# Preamp.net
KiCad netlist of a schematic drawn in EAGLE
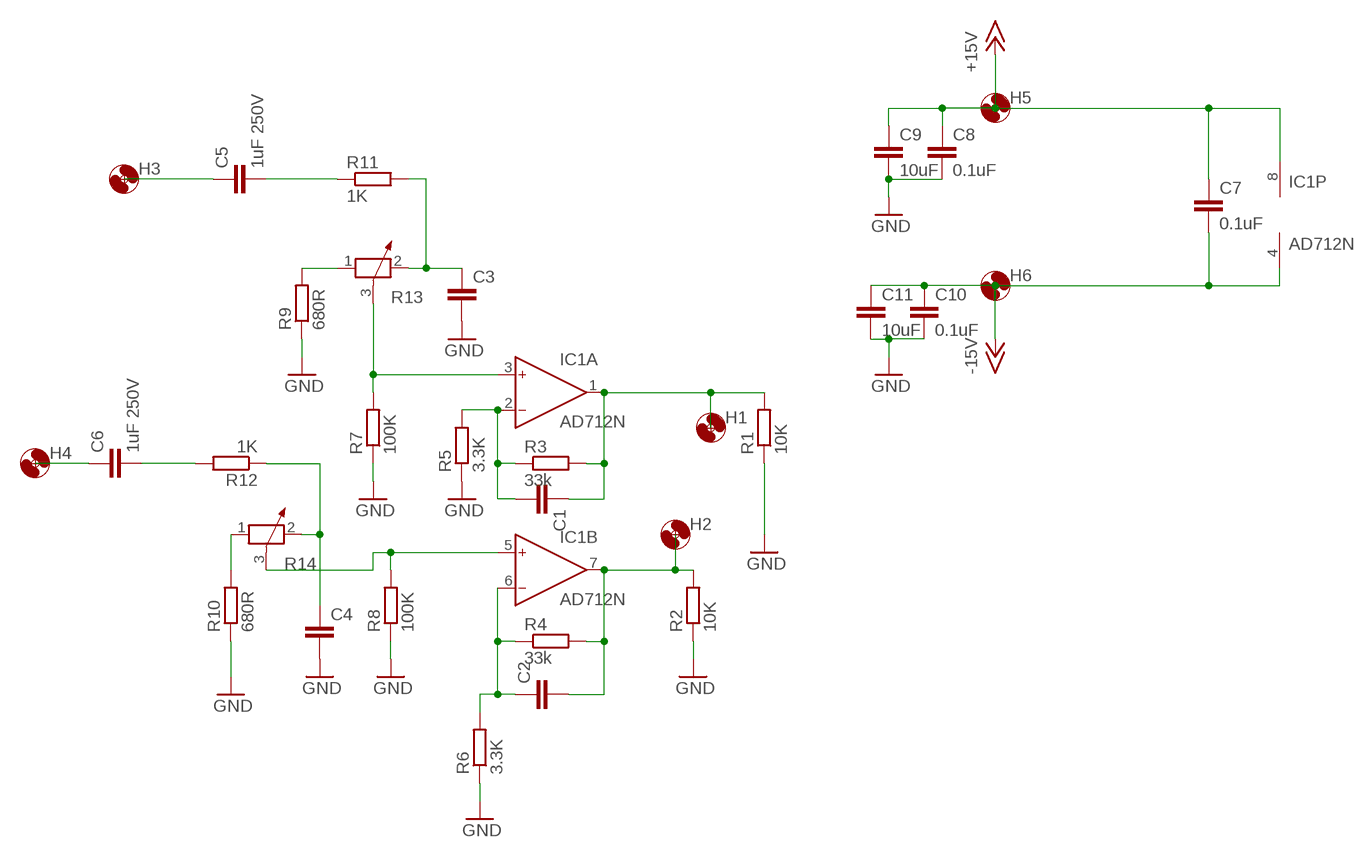
[diagram p0: schematic, sheet 1]

(export (version "E")
  (design (tool "Eeschema 10.0.6"))
  (components
    (comp (ref "C1")
      (value "C-EUC0805K")
      (footprint "eagle-import:C0805K")
      (libsource (lib "eagle-import") (part "C-EUC0805K"))
    )
    (comp (ref "C2")
      (value "C-EUC0805K")
      (footprint "eagle-import:C0805K")
      (libsource (lib "eagle-import") (part "C-EUC0805K"))
    )
    (comp (ref "C3")
      (value "C-EUC0805K")
      (footprint "eagle-import:C0805K")
      (libsource (lib "eagle-import") (part "C-EUC0805K"))
    )
    (comp (ref "C4")
      (value "C-EUC0805K")
      (footprint "eagle-import:C0805K")
      (libsource (lib "eagle-import") (part "C-EUC0805K"))
    )
    (comp (ref "C5")
      (value "1uF 250V")
      (footprint "eagle-import:C0805K")
      (libsource (lib "eagle-import") (part "C-EUC0805K"))
    )
    (comp (ref "C6")
      (value "1uF 250V")
      (footprint "eagle-import:C0805K")
      (libsource (lib "eagle-import") (part "C-EUC0805K"))
    )
    (comp (ref "C7")
      (value "0.1uF")
      (footprint "eagle-import:C0805K")
      (libsource (lib "eagle-import") (part "C-EUC0805K"))
    )
    (comp (ref "C8")
      (value "0.1uF")
      (footprint "eagle-import:C0805K")
      (libsource (lib "eagle-import") (part "C-EUC0805K"))
    )
    (comp (ref "C9")
      (value "10uF")
      (footprint "eagle-import:C0805K")
      (libsource (lib "eagle-import") (part "C-EUC0805K"))
    )
    (comp (ref "C10")
      (value "0.1uF")
      (footprint "eagle-import:C0805K")
      (libsource (lib "eagle-import") (part "C-EUC0805K"))
    )
    (comp (ref "C11")
      (value "10uF")
      (footprint "eagle-import:C0805K")
      (libsource (lib "eagle-import") (part "C-EUC0805K"))
    )
    (comp (ref "H1")
      (value "MOUNT-HOLE3.0")
      (footprint "eagle-import:3,0")
      (libsource (lib "eagle-import") (part "MOUNT-HOLE3.0"))
    )
    (comp (ref "H2")
      (value "MOUNT-HOLE3.0")
      (footprint "eagle-import:3,0")
      (libsource (lib "eagle-import") (part "MOUNT-HOLE3.0"))
    )
    (comp (ref "H3")
      (value "MOUNT-HOLE3.0")
      (footprint "eagle-import:3,0")
      (libsource (lib "eagle-import") (part "MOUNT-HOLE3.0"))
    )
    (comp (ref "H4")
      (value "MOUNT-HOLE3.0")
      (footprint "eagle-import:3,0")
      (libsource (lib "eagle-import") (part "MOUNT-HOLE3.0"))
    )
    (comp (ref "H5")
      (value "MOUNT-HOLE3.0")
      (footprint "eagle-import:3,0")
      (libsource (lib "eagle-import") (part "MOUNT-HOLE3.0"))
    )
    (comp (ref "H6")
      (value "MOUNT-HOLE3.0")
      (footprint "eagle-import:3,0")
      (libsource (lib "eagle-import") (part "MOUNT-HOLE3.0"))
    )
    (comp (ref "IC1")
      (value "AD712N")
      (footprint "eagle-import:DIL08")
      (fields (field (name "MF") "ALTERA CORPORATION") (field (name "MPN") "AD712JNZ"))
      (libsource (lib "eagle-import") (part "AD712N"))
    )
    (comp (ref "R1")
      (value "10K")
      (footprint "eagle-import:R0805W")
      (libsource (lib "eagle-import") (part "R-EU_R0805W"))
    )
    (comp (ref "R2")
      (value "10K")
      (footprint "eagle-import:R0805W")
      (libsource (lib "eagle-import") (part "R-EU_R0805W"))
    )
    (comp (ref "R3")
      (value "33k")
      (footprint "eagle-import:R0805W")
      (libsource (lib "eagle-import") (part "R-EU_R0805W"))
    )
    (comp (ref "R4")
      (value "33k")
      (footprint "eagle-import:R0805W")
      (libsource (lib "eagle-import") (part "R-EU_R0805W"))
    )
    (comp (ref "R5")
      (value "3.3K")
      (footprint "eagle-import:R0805W")
      (libsource (lib "eagle-import") (part "R-EU_R0805W"))
    )
    (comp (ref "R6")
      (value "3.3K")
      (footprint "eagle-import:R0805W")
      (libsource (lib "eagle-import") (part "R-EU_R0805W"))
    )
    (comp (ref "R7")
      (value "100K")
      (footprint "eagle-import:R0805W")
      (libsource (lib "eagle-import") (part "R-EU_R0805W"))
    )
    (comp (ref "R8")
      (value "100K")
      (footprint "eagle-import:R0805W")
      (libsource (lib "eagle-import") (part "R-EU_R0805W"))
    )
    (comp (ref "R9")
      (value "680R")
      (footprint "eagle-import:R0805W")
      (libsource (lib "eagle-import") (part "R-EU_R0805W"))
    )
    (comp (ref "R10")
      (value "680R")
      (footprint "eagle-import:R0805W")
      (libsource (lib "eagle-import") (part "R-EU_R0805W"))
    )
    (comp (ref "R11")
      (value "1K")
      (footprint "eagle-import:R0805W")
      (libsource (lib "eagle-import") (part "R-EU_R0805W"))
    )
    (comp (ref "R12")
      (value "1K")
      (footprint "eagle-import:R0805W")
      (libsource (lib "eagle-import") (part "R-EU_R0805W"))
    )
    (comp (ref "R13")
      (value "POTENTIOMETER_PT-10S")
      (footprint "eagle-import:PT-10S")
      (libsource (lib "eagle-import") (part "POTENTIOMETER_PT-10S"))
    )
    (comp (ref "R14")
      (value "POTENTIOMETER_PT-10S")
      (footprint "eagle-import:PT-10S")
      (libsource (lib "eagle-import") (part "POTENTIOMETER_PT-10S"))
    )
  )
  (nets
    (net (code "1") (name "+15V") (class "Default")
      (node (ref "C7") (pin "1") (pinfunction "1_1") (pintype "passive"))
      (node (ref "C8") (pin "1") (pinfunction "1_1") (pintype "passive"))
      (node (ref "C9") (pin "1") (pinfunction "1_1") (pintype "passive"))
      (node (ref "H5") (pin "P$1") (pinfunction "P$1_P$1") (pintype "bidirectional"))
      (node (ref "IC1") (pin "8") (pinfunction "V+_8") (pintype "power_in"))
    )
    (net (code "2") (name "-15V") (class "Default")
      (node (ref "C10") (pin "1") (pinfunction "1_1") (pintype "passive"))
      (node (ref "C11") (pin "1") (pinfunction "1_1") (pintype "passive"))
      (node (ref "C7") (pin "2") (pinfunction "2_2") (pintype "passive"))
      (node (ref "H6") (pin "P$1") (pinfunction "P$1_P$1") (pintype "bidirectional"))
      (node (ref "IC1") (pin "4") (pinfunction "V-_4") (pintype "power_in"))
    )
    (net (code "3") (name "GND") (class "Default")
      (node (ref "C10") (pin "2") (pinfunction "2_2") (pintype "passive"))
      (node (ref "C11") (pin "2") (pinfunction "2_2") (pintype "passive"))
      (node (ref "C3") (pin "2") (pinfunction "2_2") (pintype "passive"))
      (node (ref "C4") (pin "2") (pinfunction "2_2") (pintype "passive"))
      (node (ref "C8") (pin "2") (pinfunction "2_2") (pintype "passive"))
      (node (ref "C9") (pin "2") (pinfunction "2_2") (pintype "passive"))
      (node (ref "R1") (pin "1") (pinfunction "1_1") (pintype "passive"))
      (node (ref "R10") (pin "1") (pinfunction "1_1") (pintype "passive"))
      (node (ref "R2") (pin "1") (pinfunction "1_1") (pintype "passive"))
      (node (ref "R5") (pin "1") (pinfunction "1_1") (pintype "passive"))
      (node (ref "R6") (pin "1") (pinfunction "1_1") (pintype "passive"))
      (node (ref "R7") (pin "1") (pinfunction "1_1") (pintype "passive"))
      (node (ref "R8") (pin "1") (pinfunction "1_1") (pintype "passive"))
      (node (ref "R9") (pin "1") (pinfunction "1_1") (pintype "passive"))
    )
    (net (code "4") (name "Net-(C3-Pad1)") (class "Default")
      (node (ref "C3") (pin "1") (pinfunction "1_1") (pintype "passive"))
      (node (ref "R11") (pin "2") (pinfunction "2_2") (pintype "passive"))
      (node (ref "R13") (pin "2") (pinfunction "2_2") (pintype "passive"))
    )
    (net (code "5") (name "Net-(C4-Pad1)") (class "Default")
      (node (ref "C4") (pin "1") (pinfunction "1_1") (pintype "passive"))
      (node (ref "R12") (pin "1") (pinfunction "1_1") (pintype "passive"))
      (node (ref "R14") (pin "2") (pinfunction "2_2") (pintype "passive"))
    )
    (net (code "6") (name "Net-(C5-Pad1)") (class "Default")
      (node (ref "C5") (pin "1") (pinfunction "1_1") (pintype "passive"))
      (node (ref "H3") (pin "P$1") (pinfunction "P$1_P$1") (pintype "bidirectional"))
    )
    (net (code "7") (name "Net-(C5-Pad2)") (class "Default")
      (node (ref "C5") (pin "2") (pinfunction "2_2") (pintype "passive"))
      (node (ref "R11") (pin "1") (pinfunction "1_1") (pintype "passive"))
    )
    (net (code "8") (name "Net-(C6-Pad1)") (class "Default")
      (node (ref "C6") (pin "1") (pinfunction "1_1") (pintype "passive"))
      (node (ref "H4") (pin "P$1") (pinfunction "P$1_P$1") (pintype "bidirectional"))
    )
    (net (code "9") (name "Net-(C6-Pad2)") (class "Default")
      (node (ref "C6") (pin "2") (pinfunction "2_2") (pintype "passive"))
      (node (ref "R12") (pin "2") (pinfunction "2_2") (pintype "passive"))
    )
    (net (code "10") (name "Net-(IC1A-IN+)") (class "Default")
      (node (ref "IC1") (pin "3") (pinfunction "IN+_3") (pintype "input"))
      (node (ref "R13") (pin "3") (pinfunction "3_3") (pintype "passive"))
      (node (ref "R7") (pin "2") (pinfunction "2_2") (pintype "passive"))
    )
    (net (code "11") (name "Net-(IC1A-IN-)") (class "Default")
      (node (ref "C1") (pin "2") (pinfunction "2_2") (pintype "passive"))
      (node (ref "IC1") (pin "2") (pinfunction "IN-_2") (pintype "input"))
      (node (ref "R3") (pin "1") (pinfunction "1_1") (pintype "passive"))
      (node (ref "R5") (pin "2") (pinfunction "2_2") (pintype "passive"))
    )
    (net (code "12") (name "Net-(IC1A-OUT)") (class "Default")
      (node (ref "C1") (pin "1") (pinfunction "1_1") (pintype "passive"))
      (node (ref "H1") (pin "P$1") (pinfunction "P$1_P$1") (pintype "bidirectional"))
      (node (ref "IC1") (pin "1") (pinfunction "OUT_1") (pintype "output"))
      (node (ref "R1") (pin "2") (pinfunction "2_2") (pintype "passive"))
      (node (ref "R3") (pin "2") (pinfunction "2_2") (pintype "passive"))
    )
    (net (code "13") (name "Net-(IC1B-IN+)") (class "Default")
      (node (ref "IC1") (pin "5") (pinfunction "IN+_5") (pintype "input"))
      (node (ref "R14") (pin "3") (pinfunction "3_3") (pintype "passive"))
      (node (ref "R8") (pin "2") (pinfunction "2_2") (pintype "passive"))
    )
    (net (code "14") (name "Net-(IC1B-IN-)") (class "Default")
      (node (ref "C2") (pin "1") (pinfunction "1_1") (pintype "passive"))
      (node (ref "IC1") (pin "6") (pinfunction "IN-_6") (pintype "input"))
      (node (ref "R4") (pin "1") (pinfunction "1_1") (pintype "passive"))
      (node (ref "R6") (pin "2") (pinfunction "2_2") (pintype "passive"))
    )
    (net (code "15") (name "Net-(IC1B-OUT)") (class "Default")
      (node (ref "C2") (pin "2") (pinfunction "2_2") (pintype "passive"))
      (node (ref "H2") (pin "P$1") (pinfunction "P$1_P$1") (pintype "bidirectional"))
      (node (ref "IC1") (pin "7") (pinfunction "OUT_7") (pintype "output"))
      (node (ref "R2") (pin "2") (pinfunction "2_2") (pintype "passive"))
      (node (ref "R4") (pin "2") (pinfunction "2_2") (pintype "passive"))
    )
    (net (code "16") (name "Net-(R10-Pad2)") (class "Default")
      (node (ref "R10") (pin "2") (pinfunction "2_2") (pintype "passive"))
      (node (ref "R14") (pin "1") (pinfunction "1_1") (pintype "passive"))
    )
    (net (code "17") (name "Net-(R13-Pad1)") (class "Default")
      (node (ref "R13") (pin "1") (pinfunction "1_1") (pintype "passive"))
      (node (ref "R9") (pin "2") (pinfunction "2_2") (pintype "passive"))
    )
  )
)
